# RTU_B2_Battery.net
KiCad netlist of a schematic drawn in Altium Designer
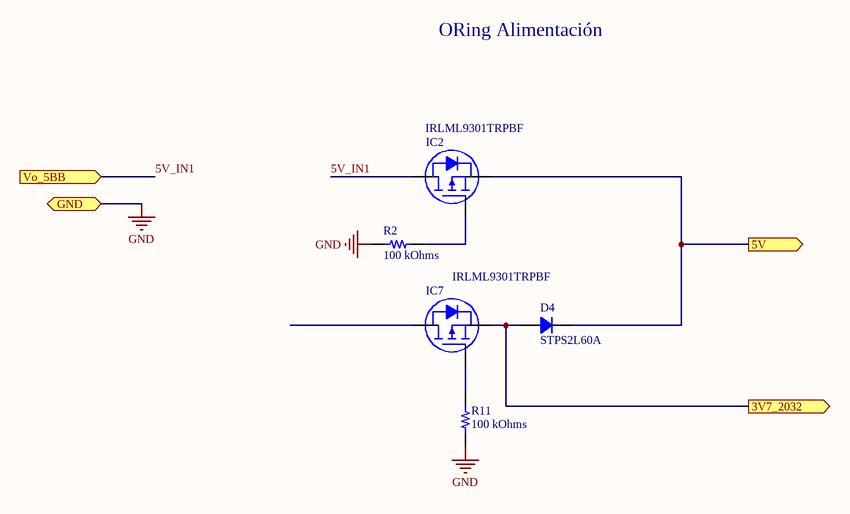
[diagram p0: RTU_B2_Battery.SchDoc]

(export (version "E")
  (design (tool "Eeschema 10.0.6"))
  (components
    (comp (ref "D4")
      (value "STPS2L60A")
      (footprint "DO214AC SMA")
      (description "DIODE SCHOTTKY 60V 2A SMA")
      (fields (field (name "MANUFACTURER") "STMicroelectronics"))
      (libsource (lib "Celestial Altium Library - altium_library") (part "Diode"))
    )
    (comp (ref "IC2")
      (value "IRLML9301TRPBF")
      (footprint "INFINEON SOT-23-3")
      (description "MOSFET P-CH 30V 3.6A SOT23")
      (fields (field (name "MANUFACTURER") "Infineon Technologies"))
      (libsource (lib "Celestial Altium Library - altium_library") (part "INFINEON MOSFET P-CH SOT-23-3"))
    )
    (comp (ref "IC7")
      (value "IRLML9301TRPBF")
      (footprint "INFINEON SOT-23-3")
      (description "MOSFET P-CH 30V 3.6A SOT23")
      (fields (field (name "MANUFACTURER") "Infineon Technologies"))
      (libsource (lib "Celestial Altium Library - altium_library") (part "INFINEON MOSFET P-CH SOT-23-3"))
    )
    (comp (ref "R2")
      (value "100 kOhms")
      (footprint "RES 0603_1608")
      (description "RES 100K OHM 0.1% 1/16W 0603")
      (fields
        (field (name "PART NUMBER") "RNCS0603BKE100K")
        (field (name "MANUFACTURER") "Stackpole Electronics Inc")
      )
      (libsource (lib "Celestial Altium Library - altium_library") (part "Resistor"))
    )
    (comp (ref "R11")
      (value "100 kOhms")
      (footprint "RES 0603_1608")
      (description "RES 100K OHM 0.1% 1/16W 0603")
      (fields
        (field (name "PART NUMBER") "RNCS0603BKE100K")
        (field (name "MANUFACTURER") "Stackpole Electronics Inc")
      )
      (libsource (lib "Celestial Altium Library - altium_library") (part "Resistor"))
    )
  )
  (nets
    (net (code "1") (name "/3V7_2032") (class "Default")
      (node (ref "D4") (pin "1") (pinfunction "1_1") (pintype "passive"))
      (node (ref "IC7") (pin "2") (pinfunction "S_2") (pintype "passive"))
    )
    (net (code "2") (name "/5V") (class "Default")
      (node (ref "D4") (pin "2") (pinfunction "2_2") (pintype "passive"))
      (node (ref "IC2") (pin "2") (pinfunction "S_2") (pintype "passive"))
    )
    (net (code "3") (name "/5V_IN1") (class "Default")
      (node (ref "IC2") (pin "3") (pinfunction "D_3") (pintype "passive"))
    )
    (net (code "4") (name "GND") (class "Default")
      (node (ref "R11") (pin "1") (pinfunction "1_1") (pintype "passive"))
      (node (ref "R2") (pin "1") (pinfunction "1_1") (pintype "passive"))
    )
    (net (code "5") (name "Net-(IC2-G)") (class "Default")
      (node (ref "IC2") (pin "1") (pinfunction "G_1") (pintype "passive"))
      (node (ref "R2") (pin "2") (pinfunction "2_2") (pintype "passive"))
    )
    (net (code "6") (name "Net-(IC7-G)") (class "Default")
      (node (ref "IC7") (pin "1") (pinfunction "G_1") (pintype "passive"))
      (node (ref "R11") (pin "2") (pinfunction "2_2") (pintype "passive"))
    )
    (net (code "7") (name "unconnected-(IC7-D-Pad3)") (class "Default")
      (node (ref "IC7") (pin "3") (pinfunction "D_3") (pintype "passive"))
    )
  )
)
